# V8502_v1.net
KiCad netlist of a schematic drawn in EAGLE
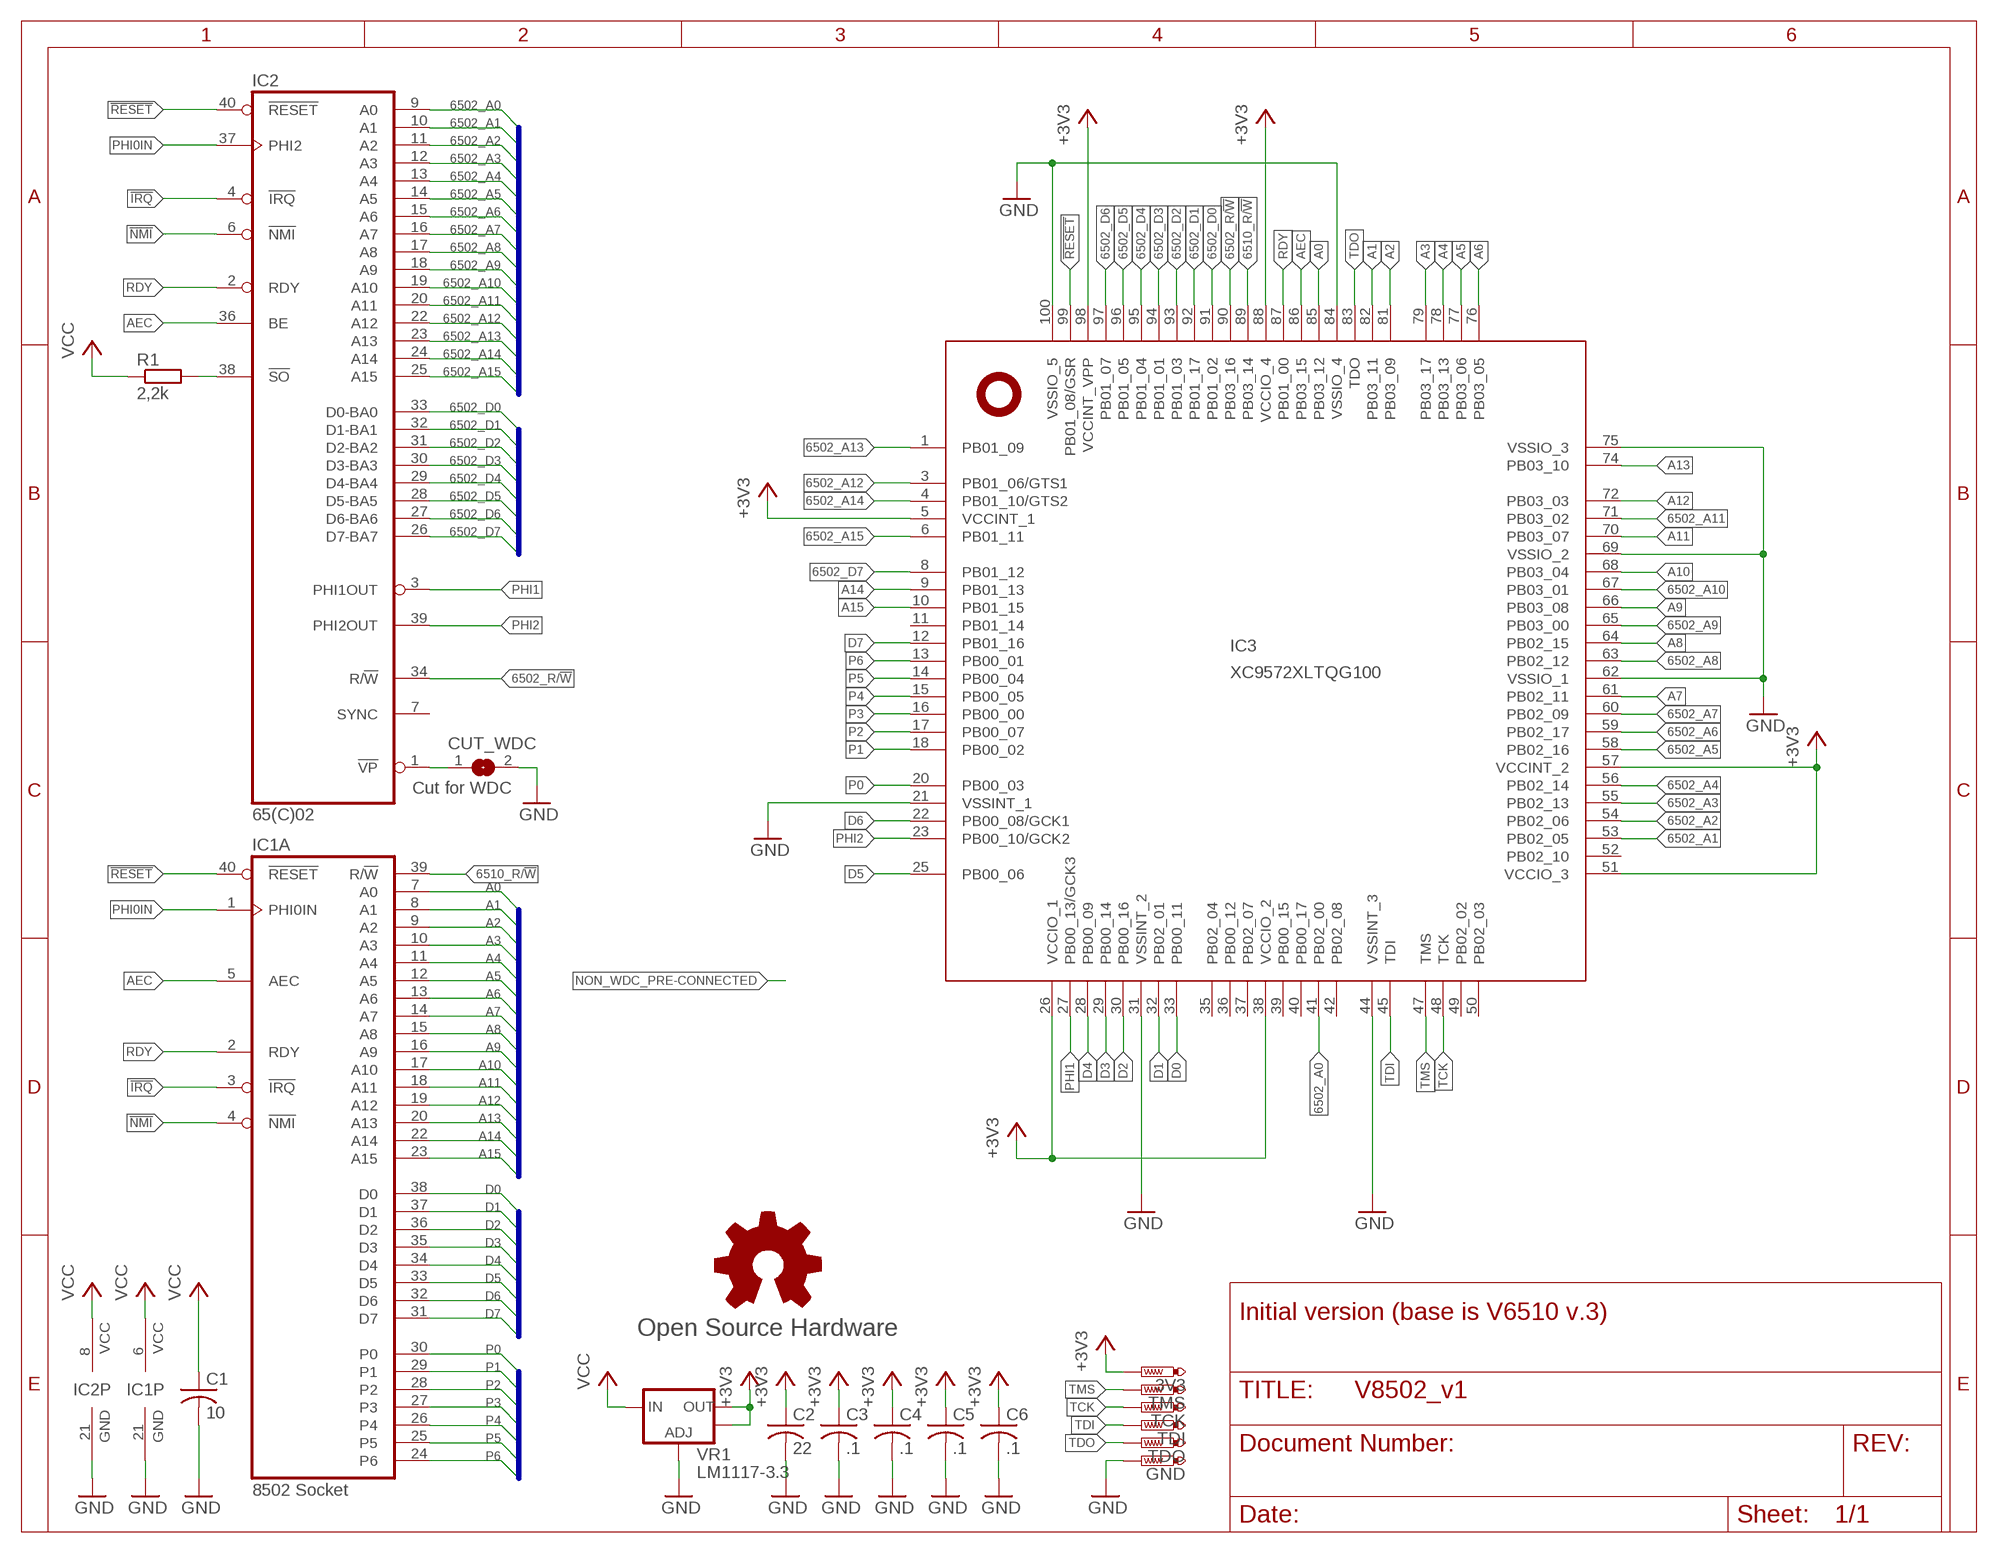
[diagram p0: schematic, sheet 1]

(export (version "E")
  (design (tool "Eeschema 10.0.6"))
  (components
    (comp (ref "3V3")
      (value "PTR1TP08R")
      (footprint "eagle-import:TP08R")
      (libsource (lib "eagle-import") (part "PTR1TP08R"))
    )
    (comp (ref "C1")
      (value "10")
      (footprint "eagle-import:C0805")
      (libsource (lib "eagle-import") (part "C-USC0805"))
    )
    (comp (ref "C2")
      (value "22")
      (footprint "eagle-import:C0805")
      (libsource (lib "eagle-import") (part "C-USC0805"))
    )
    (comp (ref "C3")
      (value ".1")
      (footprint "eagle-import:C0603")
      (libsource (lib "eagle-import") (part "C-USC0603"))
    )
    (comp (ref "C4")
      (value ".1")
      (footprint "eagle-import:C0603")
      (libsource (lib "eagle-import") (part "C-USC0603"))
    )
    (comp (ref "C5")
      (value ".1")
      (footprint "eagle-import:C0603")
      (libsource (lib "eagle-import") (part "C-USC0603"))
    )
    (comp (ref "C6")
      (value ".1")
      (footprint "eagle-import:C0603")
      (libsource (lib "eagle-import") (part "C-USC0603"))
    )
    (comp (ref "CUT_WDC")
      (value "Cut for WDC")
      (footprint "eagle-import:SJ")
      (libsource (lib "eagle-import") (part "SJ"))
    )
    (comp (ref "GND")
      (value "PTR1TP08R")
      (footprint "eagle-import:TP08R")
      (libsource (lib "eagle-import") (part "PTR1TP08R"))
    )
    (comp (ref "GOLD_ORB_SM1")
      (value "Open Source Hardware")
      (footprint "eagle-import:OSHW_5MM")
      (libsource (lib "eagle-import") (part "OSHWLOGOLOGO5MM"))
    )
    (comp (ref "IC1")
      (value "8502 Socket")
      (footprint "eagle-import:DIL40-ROUNDPAD")
      (libsource (lib "eagle-import") (part "8502"))
    )
    (comp (ref "IC2")
      (value "65(C)02")
      (footprint "eagle-import:DIL40-ROUNDPAD")
      (libsource (lib "eagle-import") (part "W65C02S-RP"))
    )
    (comp (ref "IC3")
      (value "XC9572XLTQG100")
      (footprint "eagle-import:TQFP100")
      (libsource (lib "eagle-import") (part "XC9572XLTQG100"))
    )
    (comp (ref "R1")
      (value "2,2k")
      (footprint "eagle-import:0603")
      (libsource (lib "eagle-import") (part "RESISTOR_0603"))
    )
    (comp (ref "TCK")
      (value "PTR1TP08R")
      (footprint "eagle-import:TP08R")
      (libsource (lib "eagle-import") (part "PTR1TP08R"))
    )
    (comp (ref "TDI")
      (value "PTR1TP08R")
      (footprint "eagle-import:TP08R")
      (libsource (lib "eagle-import") (part "PTR1TP08R"))
    )
    (comp (ref "TDO")
      (value "PTR1TP08R")
      (footprint "eagle-import:TP08R")
      (libsource (lib "eagle-import") (part "PTR1TP08R"))
    )
    (comp (ref "TMS")
      (value "PTR1TP08R")
      (footprint "eagle-import:TP08R")
      (libsource (lib "eagle-import") (part "PTR1TP08R"))
    )
    (comp (ref "VR1")
      (value "LM1117-3.3")
      (footprint "eagle-import:SOT223")
      (libsource (lib "eagle-import") (part "V_REG_LM1117SOT223"))
    )
  )
  (nets
    (net (code "1") (name "+3V3") (class "Default")
      (node (ref "3V3") (pin "TP") (pinfunction "TP_TP") (pintype "input"))
      (node (ref "C2") (pin "1") (pinfunction "1_1") (pintype "passive"))
      (node (ref "C3") (pin "1") (pinfunction "1_1") (pintype "passive"))
      (node (ref "C4") (pin "1") (pinfunction "1_1") (pintype "passive"))
      (node (ref "C5") (pin "1") (pinfunction "1_1") (pintype "passive"))
      (node (ref "C6") (pin "1") (pinfunction "1_1") (pintype "passive"))
      (node (ref "IC3") (pin "26") (pinfunction "VCCIO_1_26") (pintype "passive"))
      (node (ref "IC3") (pin "38") (pinfunction "VCCIO_2_38") (pintype "passive"))
      (node (ref "IC3") (pin "5") (pinfunction "VCCINT_1_5") (pintype "passive"))
      (node (ref "IC3") (pin "51") (pinfunction "VCCIO_3_51") (pintype "passive"))
      (node (ref "IC3") (pin "57") (pinfunction "VCCINT_2_57") (pintype "passive"))
      (node (ref "IC3") (pin "88") (pinfunction "VCCIO_4_88") (pintype "passive"))
      (node (ref "IC3") (pin "98") (pinfunction "VCCINT_VPP_98") (pintype "passive"))
      (node (ref "VR1") (pin "2") (pinfunction "OUT_2") (pintype "output"))
      (node (ref "VR1") (pin "4") (pinfunction "OUT_4") (pintype "output"))
    )
    (net (code "2") (name "/6502_R{slash}~{W}") (class "Default")
      (node (ref "IC2") (pin "34") (pinfunction "R/~{W}_34") (pintype "output"))
      (node (ref "IC3") (pin "90") (pinfunction "PB03_16_90") (pintype "bidirectional"))
    )
    (net (code "3") (name "/6510_R{slash}~{W}") (class "Default")
      (node (ref "IC1") (pin "39") (pinfunction "R/~{W}_39") (pintype "output"))
      (node (ref "IC3") (pin "89") (pinfunction "PB03_14_89") (pintype "bidirectional"))
    )
    (net (code "4") (name "/~{IRQ}") (class "Default")
      (node (ref "IC1") (pin "3") (pinfunction "~{IRQ}_3") (pintype "input"))
      (node (ref "IC2") (pin "4") (pinfunction "~{IRQ}_4") (pintype "input"))
    )
    (net (code "5") (name "/~{NMI}") (class "Default")
      (node (ref "IC1") (pin "4") (pinfunction "~{NMI}_4") (pintype "input"))
      (node (ref "IC2") (pin "6") (pinfunction "~{NMI}_6") (pintype "input"))
    )
    (net (code "6") (name "/~{RESET}") (class "Default")
      (node (ref "IC1") (pin "40") (pinfunction "~{RESET}_40") (pintype "input"))
      (node (ref "IC2") (pin "40") (pinfunction "~{RESET}_40") (pintype "input"))
      (node (ref "IC3") (pin "99") (pinfunction "PB01_08/GSR_99") (pintype "bidirectional"))
    )
    (net (code "7") (name "6502_A0") (class "Default")
      (node (ref "IC2") (pin "9") (pinfunction "A0_9") (pintype "tri_state"))
      (node (ref "IC3") (pin "41") (pinfunction "PB02_00_41") (pintype "bidirectional"))
    )
    (net (code "8") (name "6502_A1") (class "Default")
      (node (ref "IC2") (pin "10") (pinfunction "A1_10") (pintype "tri_state"))
      (node (ref "IC3") (pin "53") (pinfunction "PB02_05_53") (pintype "bidirectional"))
    )
    (net (code "9") (name "6502_A2") (class "Default")
      (node (ref "IC2") (pin "11") (pinfunction "A2_11") (pintype "tri_state"))
      (node (ref "IC3") (pin "54") (pinfunction "PB02_06_54") (pintype "bidirectional"))
    )
    (net (code "10") (name "6502_A3") (class "Default")
      (node (ref "IC2") (pin "12") (pinfunction "A3_12") (pintype "tri_state"))
      (node (ref "IC3") (pin "55") (pinfunction "PB02_13_55") (pintype "bidirectional"))
    )
    (net (code "11") (name "6502_A4") (class "Default")
      (node (ref "IC2") (pin "13") (pinfunction "A4_13") (pintype "tri_state"))
      (node (ref "IC3") (pin "56") (pinfunction "PB02_14_56") (pintype "bidirectional"))
    )
    (net (code "12") (name "6502_A5") (class "Default")
      (node (ref "IC2") (pin "14") (pinfunction "A5_14") (pintype "tri_state"))
      (node (ref "IC3") (pin "58") (pinfunction "PB02_16_58") (pintype "bidirectional"))
    )
    (net (code "13") (name "6502_A6") (class "Default")
      (node (ref "IC2") (pin "15") (pinfunction "A6_15") (pintype "tri_state"))
      (node (ref "IC3") (pin "59") (pinfunction "PB02_17_59") (pintype "bidirectional"))
    )
    (net (code "14") (name "6502_A7") (class "Default")
      (node (ref "IC2") (pin "16") (pinfunction "A7_16") (pintype "tri_state"))
      (node (ref "IC3") (pin "60") (pinfunction "PB02_09_60") (pintype "bidirectional"))
    )
    (net (code "15") (name "6502_A8") (class "Default")
      (node (ref "IC2") (pin "17") (pinfunction "A8_17") (pintype "tri_state"))
      (node (ref "IC3") (pin "63") (pinfunction "PB02_12_63") (pintype "bidirectional"))
    )
    (net (code "16") (name "6502_A9") (class "Default")
      (node (ref "IC2") (pin "18") (pinfunction "A9_18") (pintype "tri_state"))
      (node (ref "IC3") (pin "65") (pinfunction "PB03_00_65") (pintype "bidirectional"))
    )
    (net (code "17") (name "6502_A10") (class "Default")
      (node (ref "IC2") (pin "19") (pinfunction "A10_19") (pintype "tri_state"))
      (node (ref "IC3") (pin "67") (pinfunction "PB03_01_67") (pintype "bidirectional"))
    )
    (net (code "18") (name "6502_A11") (class "Default")
      (node (ref "IC2") (pin "20") (pinfunction "A11_20") (pintype "tri_state"))
      (node (ref "IC3") (pin "71") (pinfunction "PB03_02_71") (pintype "bidirectional"))
    )
    (net (code "19") (name "6502_A12") (class "Default")
      (node (ref "IC2") (pin "22") (pinfunction "A12_22") (pintype "tri_state"))
      (node (ref "IC3") (pin "3") (pinfunction "PB01_06/GTS1_3") (pintype "bidirectional"))
    )
    (net (code "20") (name "6502_A13") (class "Default")
      (node (ref "IC2") (pin "23") (pinfunction "A13_23") (pintype "tri_state"))
      (node (ref "IC3") (pin "1") (pinfunction "PB01_09_1") (pintype "bidirectional"))
    )
    (net (code "21") (name "6502_A14") (class "Default")
      (node (ref "IC2") (pin "24") (pinfunction "A14_24") (pintype "tri_state"))
      (node (ref "IC3") (pin "4") (pinfunction "PB01_10/GTS2_4") (pintype "bidirectional"))
    )
    (net (code "22") (name "6502_A15") (class "Default")
      (node (ref "IC2") (pin "25") (pinfunction "A15_25") (pintype "tri_state"))
      (node (ref "IC3") (pin "6") (pinfunction "PB01_11_6") (pintype "bidirectional"))
    )
    (net (code "23") (name "6502_D0") (class "Default")
      (node (ref "IC2") (pin "33") (pinfunction "D0-BA0_33") (pintype "bidirectional"))
      (node (ref "IC3") (pin "91") (pinfunction "PB01_02_91") (pintype "bidirectional"))
    )
    (net (code "24") (name "6502_D1") (class "Default")
      (node (ref "IC2") (pin "32") (pinfunction "D1-BA1_32") (pintype "bidirectional"))
      (node (ref "IC3") (pin "92") (pinfunction "PB01_17_92") (pintype "bidirectional"))
    )
    (net (code "25") (name "6502_D2") (class "Default")
      (node (ref "IC2") (pin "31") (pinfunction "D2-BA2_31") (pintype "bidirectional"))
      (node (ref "IC3") (pin "93") (pinfunction "PB01_03_93") (pintype "bidirectional"))
    )
    (net (code "26") (name "6502_D3") (class "Default")
      (node (ref "IC2") (pin "30") (pinfunction "D3-BA3_30") (pintype "bidirectional"))
      (node (ref "IC3") (pin "94") (pinfunction "PB01_01_94") (pintype "bidirectional"))
    )
    (net (code "27") (name "6502_D4") (class "Default")
      (node (ref "IC2") (pin "29") (pinfunction "D4-BA4_29") (pintype "bidirectional"))
      (node (ref "IC3") (pin "95") (pinfunction "PB01_04_95") (pintype "bidirectional"))
    )
    (net (code "28") (name "6502_D5") (class "Default")
      (node (ref "IC2") (pin "28") (pinfunction "D5-BA5_28") (pintype "bidirectional"))
      (node (ref "IC3") (pin "96") (pinfunction "PB01_05_96") (pintype "bidirectional"))
    )
    (net (code "29") (name "6502_D6") (class "Default")
      (node (ref "IC2") (pin "27") (pinfunction "D6-BA6_27") (pintype "bidirectional"))
      (node (ref "IC3") (pin "97") (pinfunction "PB01_07_97") (pintype "bidirectional"))
    )
    (net (code "30") (name "6502_D7") (class "Default")
      (node (ref "IC2") (pin "26") (pinfunction "D7-BA7_26") (pintype "bidirectional"))
      (node (ref "IC3") (pin "8") (pinfunction "PB01_12_8") (pintype "bidirectional"))
    )
    (net (code "31") (name "A0") (class "Default")
      (node (ref "IC1") (pin "7") (pinfunction "A0_7") (pintype "output"))
      (node (ref "IC3") (pin "85") (pinfunction "PB03_12_85") (pintype "bidirectional"))
    )
    (net (code "32") (name "A1") (class "Default")
      (node (ref "IC1") (pin "8") (pinfunction "A1_8") (pintype "output"))
      (node (ref "IC3") (pin "82") (pinfunction "PB03_11_82") (pintype "bidirectional"))
    )
    (net (code "33") (name "A2") (class "Default")
      (node (ref "IC1") (pin "9") (pinfunction "A2_9") (pintype "output"))
      (node (ref "IC3") (pin "81") (pinfunction "PB03_09_81") (pintype "bidirectional"))
    )
    (net (code "34") (name "A3") (class "Default")
      (node (ref "IC1") (pin "10") (pinfunction "A3_10") (pintype "output"))
      (node (ref "IC3") (pin "79") (pinfunction "PB03_17_79") (pintype "bidirectional"))
    )
    (net (code "35") (name "A4") (class "Default")
      (node (ref "IC1") (pin "11") (pinfunction "A4_11") (pintype "output"))
      (node (ref "IC3") (pin "78") (pinfunction "PB03_13_78") (pintype "bidirectional"))
    )
    (net (code "36") (name "A5") (class "Default")
      (node (ref "IC1") (pin "12") (pinfunction "A5_12") (pintype "output"))
      (node (ref "IC3") (pin "77") (pinfunction "PB03_06_77") (pintype "bidirectional"))
    )
    (net (code "37") (name "A6") (class "Default")
      (node (ref "IC1") (pin "13") (pinfunction "A6_13") (pintype "output"))
      (node (ref "IC3") (pin "76") (pinfunction "PB03_05_76") (pintype "bidirectional"))
    )
    (net (code "38") (name "A7") (class "Default")
      (node (ref "IC1") (pin "14") (pinfunction "A7_14") (pintype "output"))
      (node (ref "IC3") (pin "61") (pinfunction "PB02_11_61") (pintype "bidirectional"))
    )
    (net (code "39") (name "A8") (class "Default")
      (node (ref "IC1") (pin "15") (pinfunction "A8_15") (pintype "output"))
      (node (ref "IC3") (pin "64") (pinfunction "PB02_15_64") (pintype "bidirectional"))
    )
    (net (code "40") (name "A9") (class "Default")
      (node (ref "IC1") (pin "16") (pinfunction "A9_16") (pintype "output"))
      (node (ref "IC3") (pin "66") (pinfunction "PB03_08_66") (pintype "bidirectional"))
    )
    (net (code "41") (name "A10") (class "Default")
      (node (ref "IC1") (pin "17") (pinfunction "A10_17") (pintype "output"))
      (node (ref "IC3") (pin "68") (pinfunction "PB03_04_68") (pintype "bidirectional"))
    )
    (net (code "42") (name "A11") (class "Default")
      (node (ref "IC1") (pin "18") (pinfunction "A11_18") (pintype "output"))
      (node (ref "IC3") (pin "70") (pinfunction "PB03_07_70") (pintype "bidirectional"))
    )
    (net (code "43") (name "A12") (class "Default")
      (node (ref "IC1") (pin "19") (pinfunction "A12_19") (pintype "output"))
      (node (ref "IC3") (pin "72") (pinfunction "PB03_03_72") (pintype "bidirectional"))
    )
    (net (code "44") (name "A13") (class "Default")
      (node (ref "IC1") (pin "20") (pinfunction "A13_20") (pintype "output"))
      (node (ref "IC3") (pin "74") (pinfunction "PB03_10_74") (pintype "bidirectional"))
    )
    (net (code "45") (name "A14") (class "Default")
      (node (ref "IC1") (pin "22") (pinfunction "A14_22") (pintype "output"))
      (node (ref "IC3") (pin "9") (pinfunction "PB01_13_9") (pintype "bidirectional"))
    )
    (net (code "46") (name "A15") (class "Default")
      (node (ref "IC1") (pin "23") (pinfunction "A15_23") (pintype "output"))
      (node (ref "IC3") (pin "10") (pinfunction "PB01_15_10") (pintype "bidirectional"))
    )
    (net (code "47") (name "AEC") (class "Default")
      (node (ref "IC1") (pin "5") (pinfunction "AEC_5") (pintype "input"))
      (node (ref "IC2") (pin "36") (pinfunction "BE_36") (pintype "input"))
      (node (ref "IC3") (pin "86") (pinfunction "PB03_15_86") (pintype "bidirectional"))
    )
    (net (code "48") (name "D0") (class "Default")
      (node (ref "IC1") (pin "38") (pinfunction "D0_38") (pintype "bidirectional"))
      (node (ref "IC3") (pin "33") (pinfunction "PB00_11_33") (pintype "bidirectional"))
    )
    (net (code "49") (name "D1") (class "Default")
      (node (ref "IC1") (pin "37") (pinfunction "D1_37") (pintype "bidirectional"))
      (node (ref "IC3") (pin "32") (pinfunction "PB02_01_32") (pintype "bidirectional"))
    )
    (net (code "50") (name "D2") (class "Default")
      (node (ref "IC1") (pin "36") (pinfunction "D2_36") (pintype "bidirectional"))
      (node (ref "IC3") (pin "30") (pinfunction "PB00_16_30") (pintype "bidirectional"))
    )
    (net (code "51") (name "D3") (class "Default")
      (node (ref "IC1") (pin "35") (pinfunction "D3_35") (pintype "bidirectional"))
      (node (ref "IC3") (pin "29") (pinfunction "PB00_14_29") (pintype "bidirectional"))
    )
    (net (code "52") (name "D4") (class "Default")
      (node (ref "IC1") (pin "34") (pinfunction "D4_34") (pintype "bidirectional"))
      (node (ref "IC3") (pin "28") (pinfunction "PB00_09_28") (pintype "bidirectional"))
    )
    (net (code "53") (name "D5") (class "Default")
      (node (ref "IC1") (pin "33") (pinfunction "D5_33") (pintype "bidirectional"))
      (node (ref "IC3") (pin "25") (pinfunction "PB00_06_25") (pintype "bidirectional"))
    )
    (net (code "54") (name "D6") (class "Default")
      (node (ref "IC1") (pin "32") (pinfunction "D6_32") (pintype "bidirectional"))
      (node (ref "IC3") (pin "22") (pinfunction "PB00_08/GCK1_22") (pintype "bidirectional"))
    )
    (net (code "55") (name "D7") (class "Default")
      (node (ref "IC1") (pin "31") (pinfunction "D7_31") (pintype "bidirectional"))
      (node (ref "IC3") (pin "12") (pinfunction "PB01_16_12") (pintype "bidirectional"))
    )
    (net (code "56") (name "GND") (class "Default")
      (node (ref "C1") (pin "2") (pinfunction "2_2") (pintype "passive"))
      (node (ref "C2") (pin "2") (pinfunction "2_2") (pintype "passive"))
      (node (ref "C3") (pin "2") (pinfunction "2_2") (pintype "passive"))
      (node (ref "C4") (pin "2") (pinfunction "2_2") (pintype "passive"))
      (node (ref "C5") (pin "2") (pinfunction "2_2") (pintype "passive"))
      (node (ref "C6") (pin "2") (pinfunction "2_2") (pintype "passive"))
      (node (ref "CUT_WDC") (pin "2") (pinfunction "2_2") (pintype "passive"))
      (node (ref "GND") (pin "TP") (pinfunction "TP_TP") (pintype "input"))
      (node (ref "IC1") (pin "21") (pinfunction "GND_21") (pintype "power_in"))
      (node (ref "IC2") (pin "21") (pinfunction "GND_21") (pintype "power_in"))
      (node (ref "IC3") (pin "100") (pinfunction "VSSIO_5_100") (pintype "passive"))
      (node (ref "IC3") (pin "21") (pinfunction "VSSINT_1_21") (pintype "passive"))
      (node (ref "IC3") (pin "31") (pinfunction "VSSINT_2_31") (pintype "passive"))
      (node (ref "IC3") (pin "44") (pinfunction "VSSINT_3_44") (pintype "passive"))
      (node (ref "IC3") (pin "62") (pinfunction "VSSIO_1_62") (pintype "passive"))
      (node (ref "IC3") (pin "69") (pinfunction "VSSIO_2_69") (pintype "passive"))
      (node (ref "IC3") (pin "75") (pinfunction "VSSIO_3_75") (pintype "passive"))
      (node (ref "IC3") (pin "84") (pinfunction "VSSIO_4_84") (pintype "passive"))
      (node (ref "VR1") (pin "1") (pinfunction "ADJ_1") (pintype "input"))
    )
    (net (code "58") (name "Net-(IC2A-~{SO})") (class "Default")
      (node (ref "IC2") (pin "38") (pinfunction "~{SO}_38") (pintype "output"))
      (node (ref "R1") (pin "2") (pinfunction "2_2") (pintype "passive"))
    )
    (net (code "59") (name "Net-(IC2A-~{VP})") (class "Default")
      (node (ref "CUT_WDC") (pin "1") (pinfunction "1_1") (pintype "passive"))
      (node (ref "IC2") (pin "1") (pinfunction "~{VP}_1") (pintype "output"))
    )
    (net (code "60") (name "P0") (class "Default")
      (node (ref "IC1") (pin "30") (pinfunction "P0_30") (pintype "output"))
      (node (ref "IC3") (pin "20") (pinfunction "PB00_03_20") (pintype "bidirectional"))
    )
    (net (code "61") (name "P1") (class "Default")
      (node (ref "IC1") (pin "29") (pinfunction "P1_29") (pintype "output"))
      (node (ref "IC3") (pin "18") (pinfunction "PB00_02_18") (pintype "bidirectional"))
    )
    (net (code "62") (name "P2") (class "Default")
      (node (ref "IC1") (pin "28") (pinfunction "P2_28") (pintype "output"))
      (node (ref "IC3") (pin "17") (pinfunction "PB00_07_17") (pintype "bidirectional"))
    )
    (net (code "63") (name "P3") (class "Default")
      (node (ref "IC1") (pin "27") (pinfunction "P3_27") (pintype "output"))
      (node (ref "IC3") (pin "16") (pinfunction "PB00_00_16") (pintype "bidirectional"))
    )
    (net (code "64") (name "P4") (class "Default")
      (node (ref "IC1") (pin "26") (pinfunction "P4_26") (pintype "output"))
      (node (ref "IC3") (pin "15") (pinfunction "PB00_05_15") (pintype "bidirectional"))
    )
    (net (code "65") (name "P5") (class "Default")
      (node (ref "IC1") (pin "25") (pinfunction "P5_25") (pintype "output"))
      (node (ref "IC3") (pin "14") (pinfunction "PB00_04_14") (pintype "bidirectional"))
    )
    (net (code "66") (name "P6") (class "Default")
      (node (ref "IC1") (pin "24") (pinfunction "P6_24") (pintype "output"))
      (node (ref "IC3") (pin "13") (pinfunction "PB00_01_13") (pintype "bidirectional"))
    )
    (net (code "67") (name "PHI0IN") (class "Default")
      (node (ref "IC1") (pin "1") (pinfunction "PHI0IN_1") (pintype "input"))
      (node (ref "IC2") (pin "37") (pinfunction "PHI2_37") (pintype "input"))
    )
    (net (code "68") (name "PHI1") (class "Default")
      (node (ref "IC2") (pin "3") (pinfunction "PHI1OUT_3") (pintype "input"))
      (node (ref "IC3") (pin "27") (pinfunction "PB00_13/GCK3_27") (pintype "bidirectional"))
    )
    (net (code "69") (name "PHI2") (class "Default")
      (node (ref "IC2") (pin "39") (pinfunction "PHI2OUT_39") (pintype "output"))
      (node (ref "IC3") (pin "23") (pinfunction "PB00_10/GCK2_23") (pintype "bidirectional"))
    )
    (net (code "70") (name "RDY") (class "Default")
      (node (ref "IC1") (pin "2") (pinfunction "RDY_2") (pintype "input"))
      (node (ref "IC2") (pin "2") (pinfunction "RDY_2") (pintype "bidirectional"))
      (node (ref "IC3") (pin "87") (pinfunction "PB01_00_87") (pintype "bidirectional"))
    )
    (net (code "71") (name "TCK") (class "Default")
      (node (ref "IC3") (pin "48") (pinfunction "TCK_48") (pintype "input"))
      (node (ref "TCK") (pin "TP") (pinfunction "TP_TP") (pintype "input"))
    )
    (net (code "72") (name "TDI") (class "Default")
      (node (ref "IC3") (pin "45") (pinfunction "TDI_45") (pintype "input"))
      (node (ref "TDI") (pin "TP") (pinfunction "TP_TP") (pintype "input"))
    )
    (net (code "73") (name "TDO") (class "Default")
      (node (ref "IC3") (pin "83") (pinfunction "TDO_83") (pintype "output"))
      (node (ref "TDO") (pin "TP") (pinfunction "TP_TP") (pintype "input"))
    )
    (net (code "74") (name "TMS") (class "Default")
      (node (ref "IC3") (pin "47") (pinfunction "TMS_47") (pintype "input"))
      (node (ref "TMS") (pin "TP") (pinfunction "TP_TP") (pintype "input"))
    )
    (net (code "75") (name "VCC") (class "Default")
      (node (ref "C1") (pin "1") (pinfunction "1_1") (pintype "passive"))
      (node (ref "IC1") (pin "6") (pinfunction "VCC_6") (pintype "power_in"))
      (node (ref "IC2") (pin "8") (pinfunction "VCC_8") (pintype "power_in"))
      (node (ref "R1") (pin "1") (pinfunction "1_1") (pintype "passive"))
      (node (ref "VR1") (pin "3") (pinfunction "IN_3") (pintype "input"))
    )
    (net (code "76") (name "unconnected-(IC2A-SYNC-Pad7)") (class "Default")
      (node (ref "IC2") (pin "7") (pinfunction "SYNC_7") (pintype "output"))
    )
    (net (code "77") (name "unconnected-(IC3-PB00_12-Pad36)") (class "Default")
      (node (ref "IC3") (pin "36") (pinfunction "PB00_12_36") (pintype "bidirectional"))
    )
    (net (code "78") (name "unconnected-(IC3-PB00_15-Pad39)") (class "Default")
      (node (ref "IC3") (pin "39") (pinfunction "PB00_15_39") (pintype "bidirectional"))
    )
    (net (code "79") (name "unconnected-(IC3-PB00_17-Pad40)") (class "Default")
      (node (ref "IC3") (pin "40") (pinfunction "PB00_17_40") (pintype "bidirectional"))
    )
    (net (code "80") (name "unconnected-(IC3-PB01_14-Pad11)") (class "Default")
      (node (ref "IC3") (pin "11") (pinfunction "PB01_14_11") (pintype "bidirectional"))
    )
    (net (code "81") (name "unconnected-(IC3-PB02_02-Pad49)") (class "Default")
      (node (ref "IC3") (pin "49") (pinfunction "PB02_02_49") (pintype "bidirectional"))
    )
    (net (code "82") (name "unconnected-(IC3-PB02_03-Pad50)") (class "Default")
      (node (ref "IC3") (pin "50") (pinfunction "PB02_03_50") (pintype "bidirectional"))
    )
    (net (code "83") (name "unconnected-(IC3-PB02_04-Pad35)") (class "Default")
      (node (ref "IC3") (pin "35") (pinfunction "PB02_04_35") (pintype "bidirectional"))
    )
    (net (code "84") (name "unconnected-(IC3-PB02_07-Pad37)") (class "Default")
      (node (ref "IC3") (pin "37") (pinfunction "PB02_07_37") (pintype "bidirectional"))
    )
    (net (code "85") (name "unconnected-(IC3-PB02_08-Pad42)") (class "Default")
      (node (ref "IC3") (pin "42") (pinfunction "PB02_08_42") (pintype "bidirectional"))
    )
    (net (code "86") (name "unconnected-(IC3-PB02_10-Pad52)") (class "Default")
      (node (ref "IC3") (pin "52") (pinfunction "PB02_10_52") (pintype "bidirectional"))
    )
  )
)
